# usb2lds_v1_1.net
KiCad netlist of a schematic drawn in EAGLE
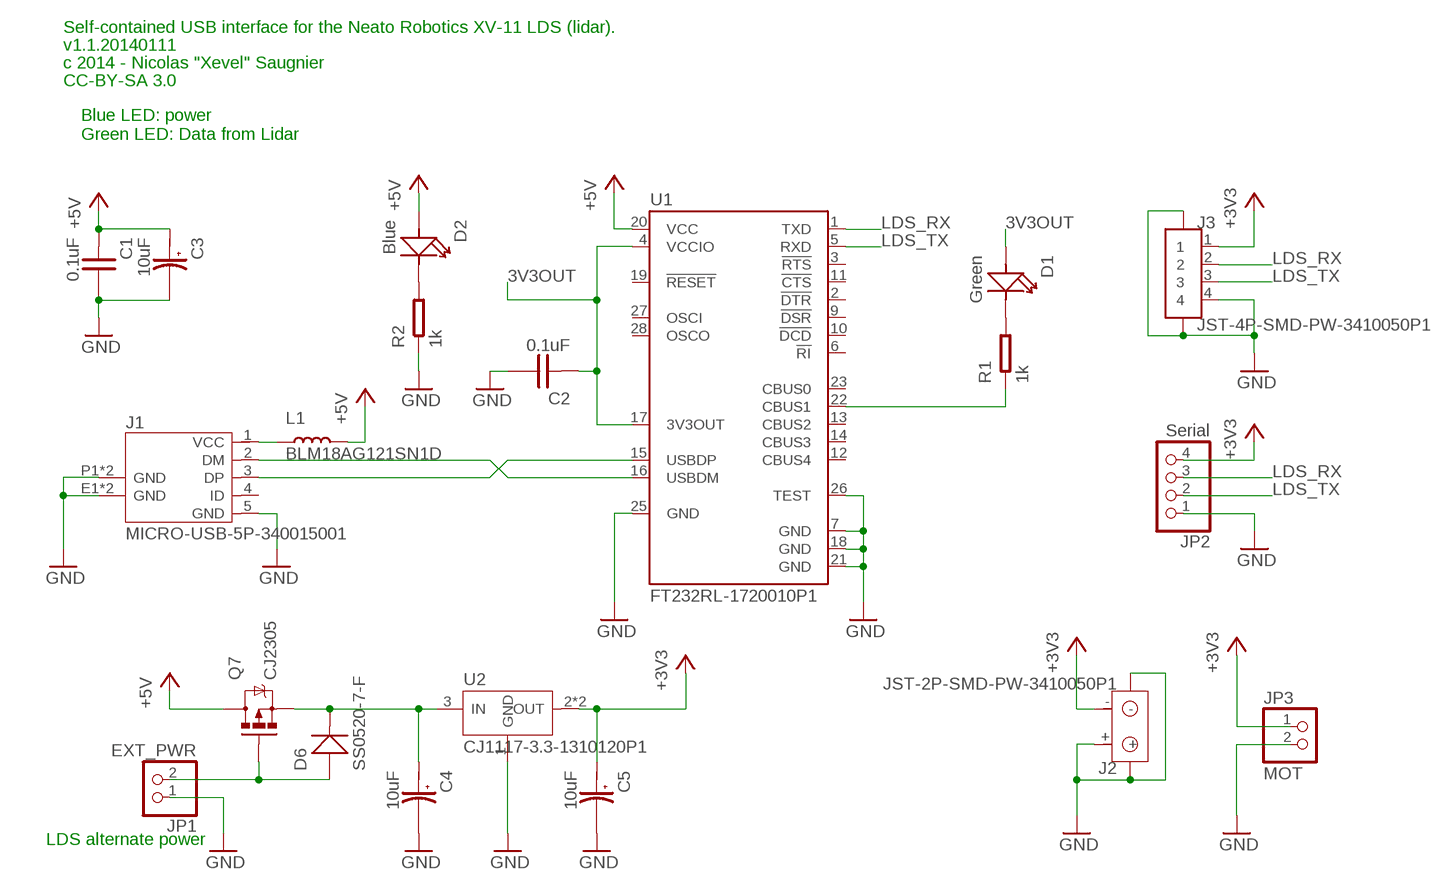
[diagram p0: schematic, sheet 1]

(export (version "E")
  (design (tool "Eeschema 10.0.6"))
  (components
    (comp (ref "C1")
      (value "0.1uF")
      (footprint "eagle-import:C0603")
      (libsource (lib "eagle-import") (part "C-0603"))
    )
    (comp (ref "C2")
      (value "0.1uF")
      (footprint "eagle-import:C0603")
      (libsource (lib "eagle-import") (part "C-0603"))
    )
    (comp (ref "C3")
      (value "10uF")
      (footprint "eagle-import:AVX-A")
      (libsource (lib "eagle-import") (part "C-POLAR-A"))
    )
    (comp (ref "C4")
      (value "10uF")
      (footprint "eagle-import:AVX-A")
      (libsource (lib "eagle-import") (part "C-POLAR-A"))
    )
    (comp (ref "C5")
      (value "10uF")
      (footprint "eagle-import:AVX-A")
      (libsource (lib "eagle-import") (part "C-POLAR-A"))
    )
    (comp (ref "D1")
      (value "Green")
      (footprint "eagle-import:LED0603")
      (libsource (lib "eagle-import") (part "LED"))
    )
    (comp (ref "D2")
      (value "Blue")
      (footprint "eagle-import:LED0603")
      (libsource (lib "eagle-import") (part "LED"))
    )
    (comp (ref "D6")
      (value "SS0520-7-F")
      (footprint "eagle-import:SOD123")
      (libsource (lib "eagle-import") (part "D-SOD-123"))
    )
    (comp (ref "J1")
      (value "MICRO-USB-5P-340015001")
      (footprint "eagle-import:B-SMD-5P")
      (libsource (lib "eagle-import") (part "MICRO-USB-5P-340015001"))
    )
    (comp (ref "J2")
      (value "JST-2P-SMD-PW-3410050P1")
      (footprint "eagle-import:2P-SMD-2.0-90D")
      (libsource (lib "eagle-import") (part "JST-2P-SMD-PW-3410050P1"))
    )
    (comp (ref "J3")
      (value "JST-4P-SMD-PW-3410050P1")
      (footprint "eagle-import:CON-4P-SMD-2.0-90D")
      (libsource (lib "eagle-import") (part "JST-4P-SMD-PW-3410050P1"))
    )
    (comp (ref "JP1")
      (value "EXT_PWR")
      (footprint "eagle-import:1X02")
      (libsource (lib "eagle-import") (part "PINHD-1X2"))
    )
    (comp (ref "JP2")
      (value "Serial")
      (footprint "eagle-import:1X04")
      (libsource (lib "eagle-import") (part "PINHD-1X4"))
    )
    (comp (ref "JP3")
      (value "MOT")
      (footprint "eagle-import:1X02")
      (libsource (lib "eagle-import") (part "PINHD-1X2"))
    )
    (comp (ref "L1")
      (value "BLM18AG121SN1D")
      (footprint "eagle-import:L0603")
      (libsource (lib "eagle-import") (part "L-0603"))
    )
    (comp (ref "Q7")
      (value "CJ2305")
      (footprint "eagle-import:SOT-23-3_N_SSOT-3_N")
      (libsource (lib "eagle-import") (part "MOSFET_P_FDN308P"))
    )
    (comp (ref "R1")
      (value "1k")
      (footprint "eagle-import:R0603")
      (libsource (lib "eagle-import") (part "R-0603"))
    )
    (comp (ref "R2")
      (value "1k")
      (footprint "eagle-import:R0603")
      (libsource (lib "eagle-import") (part "R-0603"))
    )
    (comp (ref "U1")
      (value "FT232RL-1720010P1")
      (footprint "eagle-import:SSOP28")
      (libsource (lib "eagle-import") (part "FT232RL-1720010P1"))
    )
    (comp (ref "U2")
      (value "CJ1117-3.3-1310120P1")
      (footprint "eagle-import:SOT89")
      (libsource (lib "eagle-import") (part "CJ1117-3.3-1310120P1"))
    )
  )
  (nets
    (net (code "1") (name "+3V3") (class "Default")
      (node (ref "C5") (pin "+") (pinfunction "1_+") (pintype "bidirectional"))
      (node (ref "J2") (pin "-") (pinfunction "-_-") (pintype "bidirectional"))
      (node (ref "J3") (pin "1") (pinfunction "1_1") (pintype "bidirectional"))
      (node (ref "JP2") (pin "4") (pinfunction "4_4") (pintype "passive"))
      (node (ref "JP3") (pin "1") (pinfunction "1_1") (pintype "passive"))
      (node (ref "U2") (pin "2") (pinfunction "OUT_2") (pintype "bidirectional"))
      (node (ref "U2") (pin "4") (pinfunction "OUT_4") (pintype "bidirectional"))
    )
    (net (code "2") (name "+5V") (class "Default")
      (node (ref "C1") (pin "1") (pinfunction "1_1") (pintype "passive"))
      (node (ref "C3") (pin "+") (pinfunction "1_+") (pintype "bidirectional"))
      (node (ref "D2") (pin "+") (pinfunction "+_+") (pintype "passive"))
      (node (ref "L1") (pin "2") (pinfunction "2_2") (pintype "passive"))
      (node (ref "Q7") (pin "3") (pinfunction "D_3") (pintype "passive"))
      (node (ref "U1") (pin "20") (pinfunction "VCC_20") (pintype "input"))
    )
    (net (code "3") (name "/3V3OUT") (class "Default")
      (node (ref "C2") (pin "1") (pinfunction "1_1") (pintype "passive"))
      (node (ref "D1") (pin "+") (pinfunction "+_+") (pintype "passive"))
      (node (ref "U1") (pin "17") (pinfunction "3V3OUT_17") (pintype "input"))
      (node (ref "U1") (pin "4") (pinfunction "VCCIO_4") (pintype "input"))
    )
    (net (code "4") (name "/LDS_RX") (class "Default")
      (node (ref "J3") (pin "2") (pinfunction "2_2") (pintype "bidirectional"))
      (node (ref "JP2") (pin "3") (pinfunction "3_3") (pintype "passive"))
      (node (ref "U1") (pin "1") (pinfunction "TXD_1") (pintype "input"))
    )
    (net (code "5") (name "/LDS_TX") (class "Default")
      (node (ref "J3") (pin "3") (pinfunction "3_3") (pintype "bidirectional"))
      (node (ref "JP2") (pin "2") (pinfunction "2_2") (pintype "passive"))
      (node (ref "U1") (pin "5") (pinfunction "RXD_5") (pintype "input"))
    )
    (net (code "6") (name "GND") (class "Default")
      (node (ref "C1") (pin "2") (pinfunction "2_2") (pintype "passive"))
      (node (ref "C2") (pin "2") (pinfunction "2_2") (pintype "passive"))
      (node (ref "C3") (pin "-") (pinfunction "2_-") (pintype "bidirectional"))
      (node (ref "C4") (pin "-") (pinfunction "2_-") (pintype "bidirectional"))
      (node (ref "C5") (pin "-") (pinfunction "2_-") (pintype "bidirectional"))
      (node (ref "J1") (pin "5") (pinfunction "GND_5") (pintype "bidirectional"))
      (node (ref "J1") (pin "E1") (pinfunction "GND_E1") (pintype "bidirectional"))
      (node (ref "J1") (pin "E2") (pinfunction "GND_E2") (pintype "bidirectional"))
      (node (ref "J1") (pin "P1") (pinfunction "GND_P1") (pintype "bidirectional"))
      (node (ref "J1") (pin "P2") (pinfunction "GND_P2") (pintype "bidirectional"))
      (node (ref "J2") (pin "+") (pinfunction "+_+") (pintype "bidirectional"))
      (node (ref "J2") (pin "3") (pinfunction "3_3") (pintype "bidirectional"))
      (node (ref "J2") (pin "4") (pinfunction "4_4") (pintype "bidirectional"))
      (node (ref "J3") (pin "4") (pinfunction "4_4") (pintype "bidirectional"))
      (node (ref "J3") (pin "5") (pinfunction "5_5") (pintype "bidirectional"))
      (node (ref "J3") (pin "6") (pinfunction "6_6") (pintype "bidirectional"))
      (node (ref "JP1") (pin "1") (pinfunction "1_1") (pintype "passive"))
      (node (ref "JP2") (pin "1") (pinfunction "1_1") (pintype "passive"))
      (node (ref "JP3") (pin "2") (pinfunction "2_2") (pintype "passive"))
      (node (ref "R2") (pin "1") (pinfunction "1_1") (pintype "passive"))
      (node (ref "U1") (pin "18") (pinfunction "GND_18") (pintype "input"))
      (node (ref "U1") (pin "21") (pinfunction "GND_21") (pintype "input"))
      (node (ref "U1") (pin "25") (pinfunction "GND_25") (pintype "input"))
      (node (ref "U1") (pin "26") (pinfunction "TEST_26") (pintype "input"))
      (node (ref "U1") (pin "7") (pinfunction "GND_7") (pintype "input"))
      (node (ref "U2") (pin "1") (pinfunction "GND_1") (pintype "bidirectional"))
    )
    (net (code "7") (name "Net-(C4-1)") (class "Default")
      (node (ref "C4") (pin "+") (pinfunction "1_+") (pintype "bidirectional"))
      (node (ref "D6") (pin "-") (pinfunction "-_-") (pintype "passive"))
      (node (ref "Q7") (pin "2") (pinfunction "S_2") (pintype "passive"))
      (node (ref "U2") (pin "3") (pinfunction "IN_3") (pintype "bidirectional"))
    )
    (net (code "8") (name "Net-(D1-Pad-)") (class "Default")
      (node (ref "D1") (pin "-") (pinfunction "-_-") (pintype "passive"))
      (node (ref "R1") (pin "2") (pinfunction "2_2") (pintype "passive"))
    )
    (net (code "9") (name "Net-(D2-Pad-)") (class "Default")
      (node (ref "D2") (pin "-") (pinfunction "-_-") (pintype "passive"))
      (node (ref "R2") (pin "2") (pinfunction "2_2") (pintype "passive"))
    )
    (net (code "10") (name "Net-(J1-DM)") (class "Default")
      (node (ref "J1") (pin "2") (pinfunction "DM_2") (pintype "bidirectional"))
      (node (ref "U1") (pin "16") (pinfunction "USBDM_16") (pintype "input"))
    )
    (net (code "11") (name "Net-(J1-DP)") (class "Default")
      (node (ref "J1") (pin "3") (pinfunction "DP_3") (pintype "bidirectional"))
      (node (ref "U1") (pin "15") (pinfunction "USBDP_15") (pintype "input"))
    )
    (net (code "12") (name "Net-(J1-VCC)") (class "Default")
      (node (ref "J1") (pin "1") (pinfunction "VCC_1") (pintype "bidirectional"))
      (node (ref "L1") (pin "1") (pinfunction "1_1") (pintype "passive"))
    )
    (net (code "13") (name "Net-(Q7-G)") (class "Default")
      (node (ref "D6") (pin "+") (pinfunction "+_+") (pintype "passive"))
      (node (ref "JP1") (pin "2") (pinfunction "2_2") (pintype "passive"))
      (node (ref "Q7") (pin "1") (pinfunction "G_1") (pintype "passive"))
    )
    (net (code "14") (name "Net-(U1-CBUS1)") (class "Default")
      (node (ref "R1") (pin "1") (pinfunction "1_1") (pintype "passive"))
      (node (ref "U1") (pin "22") (pinfunction "CBUS1_22") (pintype "input"))
    )
    (net (code "15") (name "unconnected-(J1-ID-Pad4)") (class "Default")
      (node (ref "J1") (pin "4") (pinfunction "ID_4") (pintype "bidirectional"))
    )
    (net (code "16") (name "unconnected-(U1-CBUS0-Pad23)") (class "Default")
      (node (ref "U1") (pin "23") (pinfunction "CBUS0_23") (pintype "input"))
    )
    (net (code "17") (name "unconnected-(U1-CBUS2-Pad13)") (class "Default")
      (node (ref "U1") (pin "13") (pinfunction "CBUS2_13") (pintype "input"))
    )
    (net (code "18") (name "unconnected-(U1-CBUS3-Pad14)") (class "Default")
      (node (ref "U1") (pin "14") (pinfunction "CBUS3_14") (pintype "input"))
    )
    (net (code "19") (name "unconnected-(U1-CBUS4-Pad12)") (class "Default")
      (node (ref "U1") (pin "12") (pinfunction "CBUS4_12") (pintype "input"))
    )
    (net (code "20") (name "unconnected-(U1-OSCI-Pad27)") (class "Default")
      (node (ref "U1") (pin "27") (pinfunction "OSCI_27") (pintype "input"))
    )
    (net (code "21") (name "unconnected-(U1-OSCO-Pad28)") (class "Default")
      (node (ref "U1") (pin "28") (pinfunction "OSCO_28") (pintype "input"))
    )
    (net (code "22") (name "unconnected-(U1-~{CTS}-Pad11)") (class "Default")
      (node (ref "U1") (pin "11") (pinfunction "~{CTS}_11") (pintype "input"))
    )
    (net (code "23") (name "unconnected-(U1-~{DCD}-Pad10)") (class "Default")
      (node (ref "U1") (pin "10") (pinfunction "~{DCD}_10") (pintype "input"))
    )
    (net (code "24") (name "unconnected-(U1-~{DSR}-Pad9)") (class "Default")
      (node (ref "U1") (pin "9") (pinfunction "~{DSR}_9") (pintype "input"))
    )
    (net (code "25") (name "unconnected-(U1-~{DTR}-Pad2)") (class "Default")
      (node (ref "U1") (pin "2") (pinfunction "~{DTR}_2") (pintype "input"))
    )
    (net (code "26") (name "unconnected-(U1-~{RESET}-Pad19)") (class "Default")
      (node (ref "U1") (pin "19") (pinfunction "~{RESET}_19") (pintype "input"))
    )
    (net (code "27") (name "unconnected-(U1-~{RI}-Pad6)") (class "Default")
      (node (ref "U1") (pin "6") (pinfunction "~{RI}_6") (pintype "input"))
    )
    (net (code "28") (name "unconnected-(U1-~{RTS}-Pad3)") (class "Default")
      (node (ref "U1") (pin "3") (pinfunction "~{RTS}_3") (pintype "input"))
    )
  )
)
